# Kasli-SOC_USB_Serial_Quad.net
KiCad netlist of a schematic drawn in Altium Designer
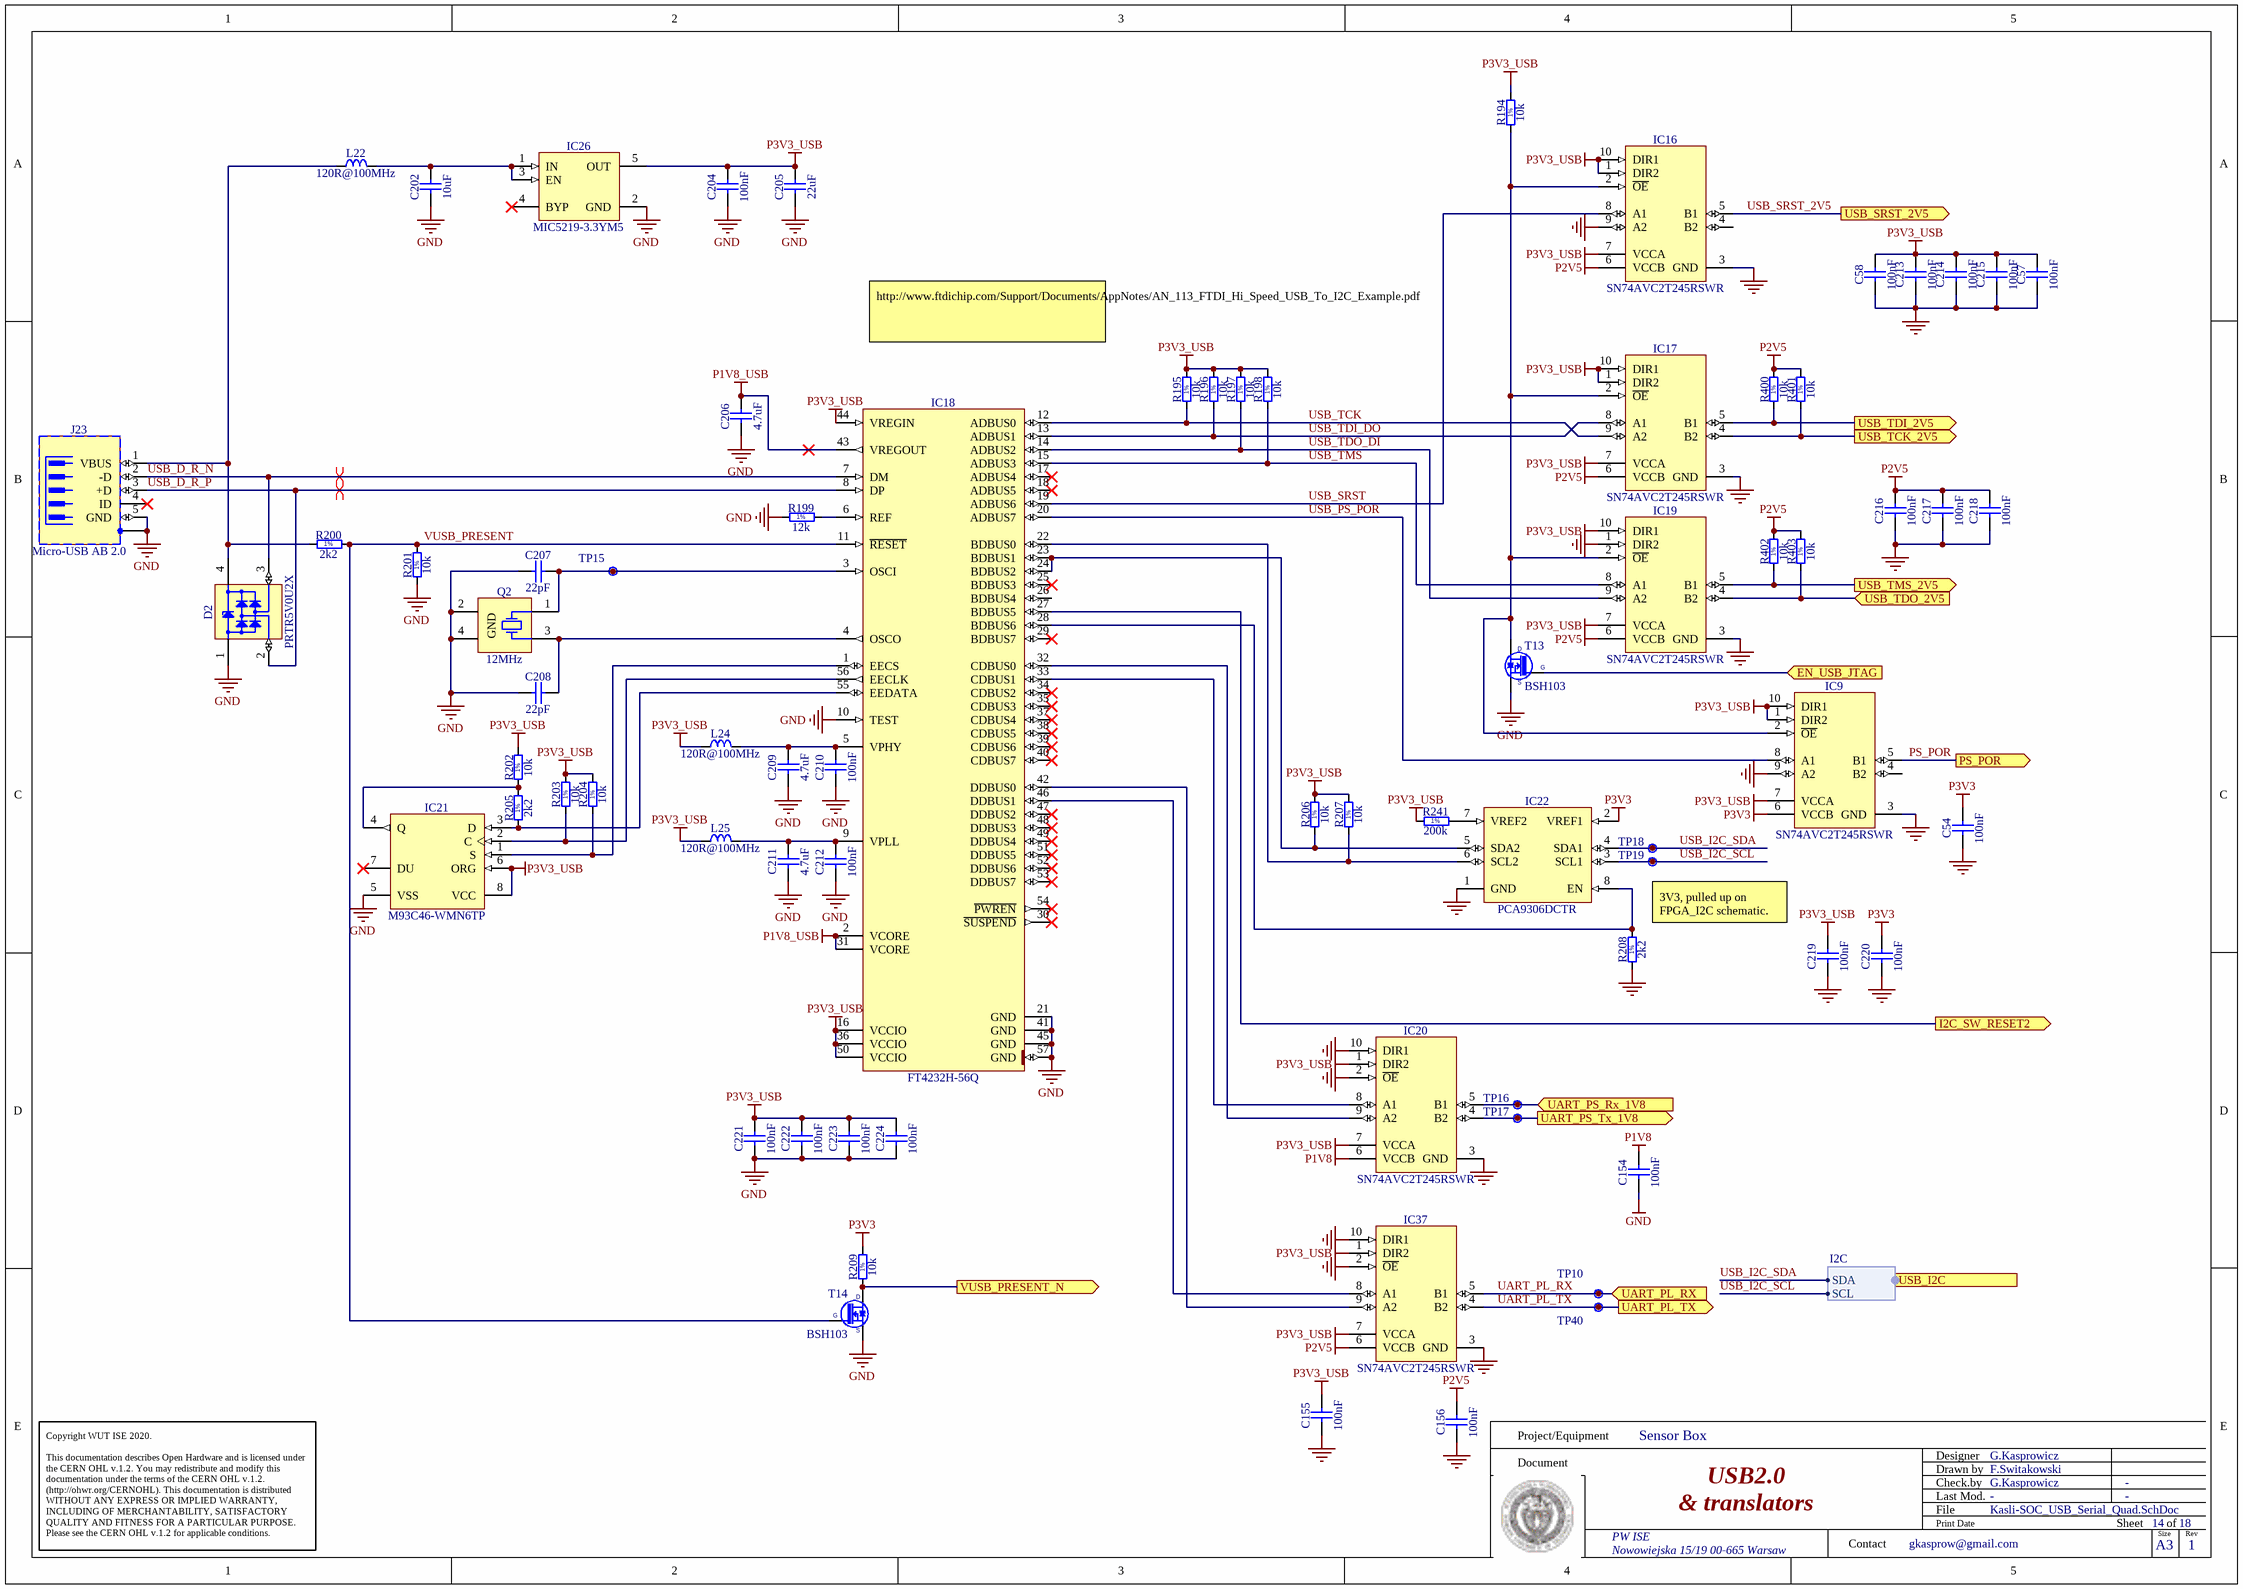
[diagram p0: Kasli-SOC_USB_Serial_Quad.SchDoc]

(export (version "E")
  (design (tool "Eeschema 10.0.6"))
  (components
    (comp (ref "C54")
      (value "100nF")
      (footprint "CAPC1005X55N")
      (description "Non-polarised capacitor")
      (fields
        (field (name "PART NUMBER") "CC0402_100NF_16V_10%_X7R")
        (field (name "VOLTAGE") "16V")
        (field (name "AUTHOR") "CERN DEM JLC")
      )
      (libsource (lib "Capacitors") (part "Capacitor - non polarized"))
    )
    (comp (ref "C57")
      (value "100nF")
      (footprint "CAPC1005X55N")
      (description "Non-polarised capacitor")
      (fields
        (field (name "PART NUMBER") "CC0402_100NF_16V_10%_X7R")
        (field (name "VOLTAGE") "16V")
        (field (name "AUTHOR") "CERN DEM JLC")
      )
      (libsource (lib "Capacitors") (part "Capacitor - non polarized"))
    )
    (comp (ref "C58")
      (value "100nF")
      (footprint "CAPC1005X55N")
      (description "Non-polarised capacitor")
      (fields
        (field (name "PART NUMBER") "CC0402_100NF_16V_10%_X7R")
        (field (name "VOLTAGE") "16V")
        (field (name "AUTHOR") "CERN DEM JLC")
      )
      (libsource (lib "Capacitors") (part "Capacitor - non polarized"))
    )
    (comp (ref "C154")
      (value "100nF")
      (footprint "CAPC1005X55N")
      (description "Non-polarised capacitor")
      (fields
        (field (name "PART NUMBER") "CC0402_100NF_16V_10%_X7R")
        (field (name "VOLTAGE") "16V")
        (field (name "AUTHOR") "CERN DEM JLC")
      )
      (libsource (lib "Capacitors") (part "Capacitor - non polarized"))
    )
    (comp (ref "C155")
      (value "100nF")
      (footprint "CAPC1005X55N")
      (description "Non-polarised capacitor")
      (fields
        (field (name "PART NUMBER") "CC0402_100NF_16V_10%_X7R")
        (field (name "VOLTAGE") "16V")
        (field (name "AUTHOR") "CERN DEM JLC")
      )
      (libsource (lib "Capacitors") (part "Capacitor - non polarized"))
    )
    (comp (ref "C156")
      (value "100nF")
      (footprint "CAPC1005X55N")
      (description "Non-polarised capacitor")
      (fields
        (field (name "PART NUMBER") "CC0402_100NF_16V_10%_X7R")
        (field (name "VOLTAGE") "16V")
        (field (name "AUTHOR") "CERN DEM JLC")
      )
      (libsource (lib "Capacitors") (part "Capacitor - non polarized"))
    )
    (comp (ref "C202")
      (value "10uF")
      (footprint "CAPC1608X87N")
      (description "Non-polarised capacitor")
      (fields
        (field (name "PART NUMBER") "CC0603_10UF_6.3V_20%_X5R")
        (field (name "VOLTAGE") "6.3V")
        (field (name "AUTHOR") "CERN DEM JLC")
      )
      (libsource (lib "Capacitors") (part "Capacitor - non polarized"))
    )
    (comp (ref "C204")
      (value "100nF")
      (footprint "CAPC0603X33N")
      (description "Non-polarised capacitor")
      (fields
        (field (name "PART NUMBER") "CC0201_100NF_6.3V_10%_X5R")
        (field (name "VOLTAGE") "6.3V")
        (field (name "AUTHOR") "CERN DEM JLC")
      )
      (libsource (lib "Capacitors") (part "Capacitor - non polarized"))
    )
    (comp (ref "C205")
      (value "22uF")
      (footprint "CAPC1709X100N")
      (description "Non-polarised capacitor")
      (fields
        (field (name "PART NUMBER") "CC0603_22UF_6.3V_20%_X5R")
        (field (name "VOLTAGE") "6.3V")
        (field (name "AUTHOR") "CERN DEM JLC")
      )
      (libsource (lib "Capacitors") (part "Capacitor - non polarized"))
    )
    (comp (ref "C206")
      (value "4.7uF")
      (footprint "CAPC2012X135N")
      (description "Non-polarised capacitor")
      (fields
        (field (name "PART NUMBER") "CC0805_4.7UF_10V_10%_X5R")
        (field (name "VOLTAGE") "10V")
        (field (name "AUTHOR") "CERN DEM JLC")
      )
      (libsource (lib "Capacitors") (part "Capacitor - non polarized"))
    )
    (comp (ref "C207")
      (value "22pF")
      (footprint "CAPC1005X55N")
      (description "Non-polarised capacitor")
      (fields
        (field (name "PART NUMBER") "CC0402_22PF_50V_5%_C0G")
        (field (name "VOLTAGE") "50V")
        (field (name "AUTHOR") "CERN DEM JLC")
      )
      (libsource (lib "Capacitors") (part "Capacitor - non polarized"))
    )
    (comp (ref "C208")
      (value "22pF")
      (footprint "CAPC1005X55N")
      (description "Non-polarised capacitor")
      (fields
        (field (name "PART NUMBER") "CC0402_22PF_50V_5%_C0G")
        (field (name "VOLTAGE") "50V")
        (field (name "AUTHOR") "CERN DEM JLC")
      )
      (libsource (lib "Capacitors") (part "Capacitor - non polarized"))
    )
    (comp (ref "C209")
      (value "4.7uF")
      (footprint "CAPC2012X135N")
      (description "Non-polarised capacitor")
      (fields
        (field (name "PART NUMBER") "CC0805_4.7UF_10V_10%_X5R")
        (field (name "VOLTAGE") "10V")
        (field (name "AUTHOR") "CERN DEM JLC")
      )
      (libsource (lib "Capacitors") (part "Capacitor - non polarized"))
    )
    (comp (ref "C210")
      (value "100nF")
      (footprint "CAPC0603X33N")
      (description "Non-polarised capacitor")
      (fields
        (field (name "PART NUMBER") "CC0201_100NF_6.3V_10%_X5R")
        (field (name "VOLTAGE") "6.3V")
        (field (name "AUTHOR") "CERN DEM JLC")
      )
      (libsource (lib "Capacitors") (part "Capacitor - non polarized"))
    )
    (comp (ref "C211")
      (value "4.7uF")
      (footprint "CAPC2012X135N")
      (description "Non-polarised capacitor")
      (fields
        (field (name "PART NUMBER") "CC0805_4.7UF_10V_10%_X5R")
        (field (name "VOLTAGE") "10V")
        (field (name "AUTHOR") "CERN DEM JLC")
      )
      (libsource (lib "Capacitors") (part "Capacitor - non polarized"))
    )
    (comp (ref "C212")
      (value "100nF")
      (footprint "CAPC0603X33N")
      (description "Non-polarised capacitor")
      (fields
        (field (name "PART NUMBER") "CC0201_100NF_6.3V_10%_X5R")
        (field (name "VOLTAGE") "6.3V")
        (field (name "AUTHOR") "CERN DEM JLC")
      )
      (libsource (lib "Capacitors") (part "Capacitor - non polarized"))
    )
    (comp (ref "C213")
      (value "100nF")
      (footprint "CAPC1005X55N")
      (description "Non-polarised capacitor")
      (fields
        (field (name "PART NUMBER") "CC0402_100NF_16V_10%_X7R")
        (field (name "VOLTAGE") "16V")
        (field (name "AUTHOR") "CERN DEM JLC")
      )
      (libsource (lib "Capacitors") (part "Capacitor - non polarized"))
    )
    (comp (ref "C214")
      (value "100nF")
      (footprint "CAPC1005X55N")
      (description "Non-polarised capacitor")
      (fields
        (field (name "PART NUMBER") "CC0402_100NF_16V_10%_X7R")
        (field (name "VOLTAGE") "16V")
        (field (name "AUTHOR") "CERN DEM JLC")
      )
      (libsource (lib "Capacitors") (part "Capacitor - non polarized"))
    )
    (comp (ref "C215")
      (value "100nF")
      (footprint "CAPC1005X55N")
      (description "Non-polarised capacitor")
      (fields
        (field (name "PART NUMBER") "CC0402_100NF_16V_10%_X7R")
        (field (name "VOLTAGE") "16V")
        (field (name "AUTHOR") "CERN DEM JLC")
      )
      (libsource (lib "Capacitors") (part "Capacitor - non polarized"))
    )
    (comp (ref "C216")
      (value "100nF")
      (footprint "CAPC1005X55N")
      (description "Non-polarised capacitor")
      (fields
        (field (name "PART NUMBER") "CC0402_100NF_16V_10%_X7R")
        (field (name "VOLTAGE") "16V")
        (field (name "AUTHOR") "CERN DEM JLC")
      )
      (libsource (lib "Capacitors") (part "Capacitor - non polarized"))
    )
    (comp (ref "C217")
      (value "100nF")
      (footprint "CAPC1005X55N")
      (description "Non-polarised capacitor")
      (fields
        (field (name "PART NUMBER") "CC0402_100NF_16V_10%_X7R")
        (field (name "VOLTAGE") "16V")
        (field (name "AUTHOR") "CERN DEM JLC")
      )
      (libsource (lib "Capacitors") (part "Capacitor - non polarized"))
    )
    (comp (ref "C218")
      (value "100nF")
      (footprint "CAPC1005X55N")
      (description "Non-polarised capacitor")
      (fields
        (field (name "PART NUMBER") "CC0402_100NF_16V_10%_X7R")
        (field (name "VOLTAGE") "16V")
        (field (name "AUTHOR") "CERN DEM JLC")
      )
      (libsource (lib "Capacitors") (part "Capacitor - non polarized"))
    )
    (comp (ref "C219")
      (value "100nF")
      (footprint "CAPC1005X55N")
      (description "Non-polarised capacitor")
      (fields
        (field (name "PART NUMBER") "CC0402_100NF_16V_10%_X7R")
        (field (name "VOLTAGE") "16V")
        (field (name "AUTHOR") "CERN DEM JLC")
      )
      (libsource (lib "Capacitors") (part "Capacitor - non polarized"))
    )
    (comp (ref "C220")
      (value "100nF")
      (footprint "CAPC1005X55N")
      (description "Non-polarised capacitor")
      (fields
        (field (name "PART NUMBER") "CC0402_100NF_16V_10%_X7R")
        (field (name "VOLTAGE") "16V")
        (field (name "AUTHOR") "CERN DEM JLC")
      )
      (libsource (lib "Capacitors") (part "Capacitor - non polarized"))
    )
    (comp (ref "C221")
      (value "100nF")
      (footprint "CAPC1005X55N")
      (description "Non-polarised capacitor")
      (fields
        (field (name "PART NUMBER") "CC0402_100NF_16V_10%_X7R")
        (field (name "VOLTAGE") "16V")
        (field (name "AUTHOR") "CERN DEM JLC")
      )
      (libsource (lib "Capacitors") (part "Capacitor - non polarized"))
    )
    (comp (ref "C222")
      (value "100nF")
      (footprint "CAPC1005X55N")
      (description "Non-polarised capacitor")
      (fields
        (field (name "PART NUMBER") "CC0402_100NF_16V_10%_X7R")
        (field (name "VOLTAGE") "16V")
        (field (name "AUTHOR") "CERN DEM JLC")
      )
      (libsource (lib "Capacitors") (part "Capacitor - non polarized"))
    )
    (comp (ref "C223")
      (value "100nF")
      (footprint "CAPC1005X55N")
      (description "Non-polarised capacitor")
      (fields
        (field (name "PART NUMBER") "CC0402_100NF_16V_10%_X7R")
        (field (name "VOLTAGE") "16V")
        (field (name "AUTHOR") "CERN DEM JLC")
      )
      (libsource (lib "Capacitors") (part "Capacitor - non polarized"))
    )
    (comp (ref "C224")
      (value "100nF")
      (footprint "CAPC1005X55N")
      (description "Non-polarised capacitor")
      (fields
        (field (name "PART NUMBER") "CC0402_100NF_16V_10%_X7R")
        (field (name "VOLTAGE") "16V")
        (field (name "AUTHOR") "CERN DEM JLC")
      )
      (libsource (lib "Capacitors") (part "Capacitor - non polarized"))
    )
    (comp (ref "D2")
      (value "PRTR5V0U2X")
      (footprint "SOT190P230X110-4N")
      (description "Ultra Low Capacitance Double Rail-to-Rail ESD Protection Diode")
      (fields
        (field (name "VOLTAGE") "5.5V")
        (field (name "MANUFACTURER") "NXP SEMICONDUCTORS")
        (field (name "AUTHOR") "CERN DEM JLC")
      )
      (libsource (lib "ICs And Semiconductors") (part "PRTR5V0U2X"))
    )
    (comp (ref "IC9")
      (value "SN74AVC2T245RSWR")
      (footprint "QFN40P140X180X55-10N")
      (description "Dual-Bit Dual-Supply Bus Transceiver With Configurable Voltage Translation and 3-State Outputs")
      (fields (field (name "MANUFACTURER") "TEXAS INSTRUMENTS") (field (name "AUTHOR") "CERN DEM JLC"))
      (libsource (lib "ICs And Semiconductors") (part "742T245"))
    )
    (comp (ref "IC16")
      (value "SN74AVC2T245RSWR")
      (footprint "QFN40P140X180X55-10N")
      (description "Dual-Bit Dual-Supply Bus Transceiver With Configurable Voltage Translation and 3-State Outputs")
      (fields (field (name "MANUFACTURER") "TEXAS INSTRUMENTS") (field (name "AUTHOR") "CERN DEM JLC"))
      (libsource (lib "ICs And Semiconductors") (part "742T245"))
    )
    (comp (ref "IC17")
      (value "SN74AVC2T245RSWR")
      (footprint "QFN40P140X180X55-10N")
      (description "Dual-Bit Dual-Supply Bus Transceiver With Configurable Voltage Translation and 3-State Outputs")
      (fields (field (name "MANUFACTURER") "TEXAS INSTRUMENTS") (field (name "AUTHOR") "CERN DEM JLC"))
      (libsource (lib "ICs And Semiconductors") (part "742T245"))
    )
    (comp (ref "IC18")
      (value "FT4232H-56Q")
      (footprint "QFN50P800X800X100-57N-S620")
      (description "Quad High Speed USB to Multipurpose UART/MPSSE IC")
      (fields
        (field (name "MANUFACTURER") "FUTURE TECHNOLOGY DEVICES INTERNATIONAL (FTDI)")
        (field (name "AUTHOR") "CERN DEM JLC")
      )
      (libsource (lib "ICs And Semiconductors") (part "FT4232H-56Q"))
    )
    (comp (ref "IC19")
      (value "SN74AVC2T245RSWR")
      (footprint "QFN40P140X180X55-10N")
      (description "Dual-Bit Dual-Supply Bus Transceiver With Configurable Voltage Translation and 3-State Outputs")
      (fields (field (name "MANUFACTURER") "TEXAS INSTRUMENTS") (field (name "AUTHOR") "CERN DEM JLC"))
      (libsource (lib "ICs And Semiconductors") (part "742T245"))
    )
    (comp (ref "IC20")
      (value "SN74AVC2T245RSWR")
      (footprint "QFN40P140X180X55-10N")
      (description "Dual-Bit Dual-Supply Bus Transceiver With Configurable Voltage Translation and 3-State Outputs")
      (fields (field (name "MANUFACTURER") "TEXAS INSTRUMENTS") (field (name "AUTHOR") "CERN DEM JLC"))
      (libsource (lib "ICs And Semiconductors") (part "742T245"))
    )
    (comp (ref "IC21")
      (value "M93C46-WMN6TP")
      (footprint "SOIC127P600X175-8N")
      (description "2.5 to 5.5 V, 1Kb (128x8) Serial Microwire Bus EEPROM")
      (fields (field (name "MANUFACTURER") "ST MICROELECTRONICS") (field (name "AUTHOR") "CERN DEM JLC"))
      (libsource (lib "ICs And Semiconductors") (part "M93C46-WMN6TP"))
    )
    (comp (ref "IC22")
      (value "PCA9306DCTR")
      (footprint "SOP65P400X130-8N")
      (description "Dual Bidirectional I2C Bus And SMBus Voltage-Level Translator")
      (fields (field (name "MANUFACTURER") "TEXAS INSTRUMENTS") (field (name "AUTHOR") "CERN DEM JLC"))
      (libsource (lib "ICs And Semiconductors") (part "PCA9306D"))
    )
    (comp (ref "IC26")
      (value "MIC5219-3.3YM5")
      (footprint "SOT95P280X145-5N")
      (description "500mA Peak Output LDO Regulator")
      (fields (field (name "MANUFACTURER") "MICROCHIP TECHNOLOGY") (field (name "AUTHOR") "CERN DEM WB"))
      (libsource (lib "ICs And Semiconductors") (part "MIC5219-X.XYM5"))
    )
    (comp (ref "IC37")
      (value "SN74AVC2T245RSWR")
      (footprint "QFN40P140X180X55-10N")
      (description "Dual-Bit Dual-Supply Bus Transceiver With Configurable Voltage Translation and 3-State Outputs")
      (fields (field (name "MANUFACTURER") "TEXAS INSTRUMENTS") (field (name "AUTHOR") "CERN DEM JLC"))
      (libsource (lib "ICs And Semiconductors") (part "742T245"))
    )
    (comp (ref "J23")
      (value "Micro-USB AB 2.0")
      (footprint "HIROSE_ZX62RD-AB-5P8")
      (description "5 Pin + 1 Shield USB Receptacle")
      (fields
        (field (name "PART NUMBER") "HIROSE_ZX62RD-AB-5P8")
        (field (name "MANUFACTURER") "HIROSE (HRS)")
        (field (name "AUTHOR") "CERN DEM JLC")
      )
      (libsource (lib "Connectors") (part "Connector USB 5 Pin + 1Shield"))
    )
    (comp (ref "L22")
      (value "120R@100MHz")
      (footprint "INDC1608X65N")
      (description "Inductor")
      (fields
        (field (name "PART NUMBER") "IND0603_MURATA_BLM18SG121TN1D")
        (field (name "POWER") "3A")
        (field (name "AUTHOR") "CERN DEM JLC")
      )
      (libsource (lib "Inductors & Transformers") (part "Inductor"))
    )
    (comp (ref "L24")
      (value "120R@100MHz")
      (footprint "INDC1608X65N")
      (description "Inductor")
      (fields
        (field (name "PART NUMBER") "IND0603_MURATA_BLM18SG121TN1D")
        (field (name "POWER") "3A")
        (field (name "AUTHOR") "CERN DEM JLC")
      )
      (libsource (lib "Inductors & Transformers") (part "Inductor"))
    )
    (comp (ref "L25")
      (value "120R@100MHz")
      (footprint "INDC1608X65N")
      (description "Inductor")
      (fields
        (field (name "PART NUMBER") "IND0603_MURATA_BLM18SG121TN1D")
        (field (name "POWER") "3A")
        (field (name "AUTHOR") "CERN DEM JLC")
      )
      (libsource (lib "Inductors & Transformers") (part "Inductor"))
    )
    (comp (ref "Q2")
      (value "12MHz")
      (footprint "XTAL_TXC_7M")
      (description "Crystal 4 pins 1=XTAL Control 2=GND3=XTAL 4=GND")
      (fields
        (field (name "PART NUMBER") "XTAL_12MHZ_TXC_7M-12.000MAAJ-T")
        (field (name "MANUFACTURER") "TXC CORPORATION")
        (field (name "AUTHOR") "CERN DEM JLC")
      )
      (libsource (lib "ICs And Semiconductors") (part "Quartz Crystal 1X 2GND 3X 4GND"))
    )
    (comp (ref "R194")
      (value "10k")
      (footprint "RESC1005X40N")
      (description "Resistor - 1%")
      (fields
        (field (name "PART NUMBER") "R0402_10K_1%_0.0625W_100PPM")
        (field (name "POWER") "0.0625W")
        (field (name "AUTHOR") "CERN DEM JLC")
      )
      (libsource (lib "Resistors") (part "Resistor - 1%"))
    )
    (comp (ref "R195")
      (value "10k")
      (footprint "RESC1005X40N")
      (description "Resistor - 1%")
      (fields
        (field (name "PART NUMBER") "R0402_10K_1%_0.0625W_100PPM")
        (field (name "POWER") "0.0625W")
        (field (name "AUTHOR") "CERN DEM JLC")
      )
      (libsource (lib "Resistors") (part "Resistor - 1%"))
    )
    (comp (ref "R196")
      (value "10k")
      (footprint "RESC1005X40N")
      (description "Resistor - 1%")
      (fields
        (field (name "PART NUMBER") "R0402_10K_1%_0.0625W_100PPM")
        (field (name "POWER") "0.0625W")
        (field (name "AUTHOR") "CERN DEM JLC")
      )
      (libsource (lib "Resistors") (part "Resistor - 1%"))
    )
    (comp (ref "R197")
      (value "10k")
      (footprint "RESC1005X40N")
      (description "Resistor - 1%")
      (fields
        (field (name "PART NUMBER") "R0402_10K_1%_0.0625W_100PPM")
        (field (name "POWER") "0.0625W")
        (field (name "AUTHOR") "CERN DEM JLC")
      )
      (libsource (lib "Resistors") (part "Resistor - 1%"))
    )
    (comp (ref "R198")
      (value "10k")
      (footprint "RESC1005X40N")
      (description "Resistor - 1%")
      (fields
        (field (name "PART NUMBER") "R0402_10K_1%_0.0625W_100PPM")
        (field (name "POWER") "0.0625W")
        (field (name "AUTHOR") "CERN DEM JLC")
      )
      (libsource (lib "Resistors") (part "Resistor - 1%"))
    )
    (comp (ref "R199")
      (value "12k")
      (footprint "RESC1005X40N")
      (description "Resistor - 1%")
      (fields
        (field (name "PART NUMBER") "R0402_12K_1%_0.0625W_100PPM")
        (field (name "POWER") "0.0625W")
        (field (name "AUTHOR") "CERN DEM JLC")
      )
      (libsource (lib "Resistors") (part "Resistor - 1%"))
    )
    (comp (ref "R200")
      (value "2k2")
      (footprint "RESC1005X40N")
      (description "Resistor - 1%")
      (fields
        (field (name "PART NUMBER") "R0402_2K2_1%_0.0625W_100PPM")
        (field (name "POWER") "0.0625W")
        (field (name "AUTHOR") "CERN DEM JLC")
      )
      (libsource (lib "Resistors") (part "Resistor - 1%"))
    )
    (comp (ref "R201")
      (value "10k")
      (footprint "RESC1005X40N")
      (description "Resistor - 1%")
      (fields
        (field (name "PART NUMBER") "R0402_10K_1%_0.0625W_100PPM")
        (field (name "POWER") "0.0625W")
        (field (name "AUTHOR") "CERN DEM JLC")
      )
      (libsource (lib "Resistors") (part "Resistor - 1%"))
    )
    (comp (ref "R202")
      (value "10k")
      (footprint "RESC1005X40N")
      (description "Resistor - 1%")
      (fields
        (field (name "PART NUMBER") "R0402_10K_1%_0.0625W_100PPM")
        (field (name "POWER") "0.0625W")
        (field (name "AUTHOR") "CERN DEM JLC")
      )
      (libsource (lib "Resistors") (part "Resistor - 1%"))
    )
    (comp (ref "R203")
      (value "10k")
      (footprint "RESC1005X40N")
      (description "Resistor - 1%")
      (fields
        (field (name "PART NUMBER") "R0402_10K_1%_0.0625W_100PPM")
        (field (name "POWER") "0.0625W")
        (field (name "AUTHOR") "CERN DEM JLC")
      )
      (libsource (lib "Resistors") (part "Resistor - 1%"))
    )
    (comp (ref "R204")
      (value "10k")
      (footprint "RESC1005X40N")
      (description "Resistor - 1%")
      (fields
        (field (name "PART NUMBER") "R0402_10K_1%_0.0625W_100PPM")
        (field (name "POWER") "0.0625W")
        (field (name "AUTHOR") "CERN DEM JLC")
      )
      (libsource (lib "Resistors") (part "Resistor - 1%"))
    )
    (comp (ref "R205")
      (value "2k2")
      (footprint "RESC1005X40N")
      (description "Resistor - 1%")
      (fields
        (field (name "PART NUMBER") "R0402_2K2_1%_0.0625W_100PPM")
        (field (name "POWER") "0.0625W")
        (field (name "AUTHOR") "CERN DEM JLC")
      )
      (libsource (lib "Resistors") (part "Resistor - 1%"))
    )
    (comp (ref "R206")
      (value "10k")
      (footprint "RESC1005X40N")
      (description "Resistor - 1%")
      (fields
        (field (name "PART NUMBER") "R0402_10K_1%_0.0625W_100PPM")
        (field (name "POWER") "0.0625W")
        (field (name "AUTHOR") "CERN DEM JLC")
      )
      (libsource (lib "Resistors") (part "Resistor - 1%"))
    )
    (comp (ref "R207")
      (value "10k")
      (footprint "RESC1005X40N")
      (description "Resistor - 1%")
      (fields
        (field (name "PART NUMBER") "R0402_10K_1%_0.0625W_100PPM")
        (field (name "POWER") "0.0625W")
        (field (name "AUTHOR") "CERN DEM JLC")
      )
      (libsource (lib "Resistors") (part "Resistor - 1%"))
    )
    (comp (ref "R208")
      (value "2k2")
      (footprint "RESC1005X40N")
      (description "Resistor - 1%")
      (fields
        (field (name "PART NUMBER") "R0402_2K2_1%_0.0625W_100PPM")
        (field (name "POWER") "0.0625W")
        (field (name "AUTHOR") "CERN DEM JLC")
      )
      (libsource (lib "Resistors") (part "Resistor - 1%"))
    )
    (comp (ref "R209")
      (value "10k")
      (footprint "RESC1005X40N")
      (description "Resistor - 1%")
      (fields
        (field (name "PART NUMBER") "R0402_10K_1%_0.0625W_100PPM")
        (field (name "POWER") "0.0625W")
        (field (name "AUTHOR") "CERN DEM JLC")
      )
      (libsource (lib "Resistors") (part "Resistor - 1%"))
    )
    (comp (ref "R241")
      (value "200k")
      (footprint "RESC1005X40N")
      (description "Resistor - 1%")
      (fields
        (field (name "PART NUMBER") "R0402_200K_1%_0.0625W_100PPM")
        (field (name "POWER") "0.0625W")
        (field (name "AUTHOR") "CERN DEM JLC")
      )
      (libsource (lib "Resistors") (part "Resistor - 1%"))
    )
    (comp (ref "R400")
      (value "10k")
      (footprint "RESC1005X40N")
      (description "Resistor - 1%")
      (fields
        (field (name "PART NUMBER") "R0402_10K_1%_0.0625W_100PPM")
        (field (name "POWER") "0.0625W")
        (field (name "AUTHOR") "CERN DEM JLC")
      )
      (libsource (lib "Resistors") (part "Resistor - 1%"))
    )
    (comp (ref "R401")
      (value "10k")
      (footprint "RESC1005X40N")
      (description "Resistor - 1%")
      (fields
        (field (name "PART NUMBER") "R0402_10K_1%_0.0625W_100PPM")
        (field (name "POWER") "0.0625W")
        (field (name "AUTHOR") "CERN DEM JLC")
      )
      (libsource (lib "Resistors") (part "Resistor - 1%"))
    )
    (comp (ref "R402")
      (value "10k")
      (footprint "RESC1005X40N")
      (description "Resistor - 1%")
      (fields
        (field (name "PART NUMBER") "R0402_10K_1%_0.0625W_100PPM")
        (field (name "POWER") "0.0625W")
        (field (name "AUTHOR") "CERN DEM JLC")
      )
      (libsource (lib "Resistors") (part "Resistor - 1%"))
    )
    (comp (ref "R403")
      (value "10k")
      (footprint "RESC1005X40N")
      (description "Resistor - 1%")
      (fields
        (field (name "PART NUMBER") "R0402_10K_1%_0.0625W_100PPM")
        (field (name "POWER") "0.0625W")
        (field (name "AUTHOR") "CERN DEM JLC")
      )
      (libsource (lib "Resistors") (part "Resistor - 1%"))
    )
    (comp (ref "T13")
      (value "BSH103")
      (footprint "SOT95P230X110-3N")
      (description "N-CHANNEL MOSFET WITH DIODE")
      (fields (field (name "MANUFACTURER") "NEXPERIA") (field (name "AUTHOR") "CERN DEM JLC"))
      (libsource (lib "") (part "N-MOSFET-D 1G 2S 3D_1"))
    )
    (comp (ref "T14")
      (value "BSH103")
      (footprint "SOT95P230X110-3N")
      (description "N-CHANNEL MOSFET WITH DIODE")
      (fields (field (name "MANUFACTURER") "NEXPERIA") (field (name "AUTHOR") "CERN DEM JLC"))
      (libsource (lib "ICs And Semiconductors") (part "N-MOSFET-D 1G 2S 3D"))
    )
    (comp (ref "TP10")
      (value "RxD")
      (footprint "TPS127")
      (description "Test Point")
      (fields (field (name "PART NUMBER") "SMD_PAD_1.27X1.27MM") (field (name "AUTHOR") "CERN DEM JLC"))
      (libsource (lib "Eletro-mechanical") (part "Test Point"))
    )
    (comp (ref "TP15")
      (value "Q2")
      (footprint "TPS127")
      (description "Test Point")
      (fields (field (name "PART NUMBER") "SMD_PAD_1.27X1.27MM") (field (name "AUTHOR") "CERN DEM JLC"))
      (libsource (lib "Eletro-mechanical") (part "Test Point"))
    )
    (comp (ref "TP16")
      (value "RxD")
      (footprint "TPS127")
      (description "Test Point")
      (fields (field (name "PART NUMBER") "SMD_PAD_1.27X1.27MM") (field (name "AUTHOR") "CERN DEM JLC"))
      (libsource (lib "Eletro-mechanical") (part "Test Point"))
    )
    (comp (ref "TP17")
      (value "TxD")
      (footprint "TPS127")
      (description "Test Point")
      (fields (field (name "PART NUMBER") "SMD_PAD_1.27X1.27MM") (field (name "AUTHOR") "CERN DEM JLC"))
      (libsource (lib "Eletro-mechanical") (part "Test Point"))
    )
    (comp (ref "TP18")
      (value "USB I2C SDA")
      (footprint "TPS127")
      (description "Test Point")
      (fields (field (name "PART NUMBER") "SMD_PAD_1.27X1.27MM") (field (name "AUTHOR") "CERN DEM JLC"))
      (libsource (lib "Eletro-mechanical") (part "Test Point"))
    )
    (comp (ref "TP19")
      (value "USB I2C SCL")
      (footprint "TPS127")
      (description "Test Point")
      (fields (field (name "PART NUMBER") "SMD_PAD_1.27X1.27MM") (field (name "AUTHOR") "CERN DEM JLC"))
      (libsource (lib "Eletro-mechanical") (part "Test Point"))
    )
    (comp (ref "TP40")
      (value "TxD")
      (footprint "TPS127")
      (description "Test Point")
      (fields (field (name "PART NUMBER") "SMD_PAD_1.27X1.27MM") (field (name "AUTHOR") "CERN DEM JLC"))
      (libsource (lib "Eletro-mechanical") (part "Test Point"))
    )
  )
  (nets
    (net (code "2") (name "/EN_USB_JTAG") (class "Default")
      (node (ref "T13") (pin "1") (pinfunction "G_1") (pintype "passive"))
    )
    (net (code "3") (name "/I2C_SW_RESET2") (class "Default")
      (node (ref "IC18") (pin "27") (pinfunction "BDBUS5_27") (pintype "bidirectional"))
    )
    (net (code "4") (name "/PS_POR") (class "Default")
      (node (ref "IC9") (pin "5") (pinfunction "B1_5") (pintype "bidirectional"))
    )
    (net (code "5") (name "/UART_PL_RX") (class "Default")
      (node (ref "IC37") (pin "5") (pinfunction "B1_5") (pintype "bidirectional"))
      (node (ref "TP10") (pin "1") (pinfunction "1_1") (pintype "bidirectional"))
    )
    (net (code "6") (name "/UART_PL_TX") (class "Default")
      (node (ref "IC37") (pin "4") (pinfunction "B2_4") (pintype "bidirectional"))
      (node (ref "TP40") (pin "1") (pinfunction "1_1") (pintype "bidirectional"))
    )
    (net (code "7") (name "/UART_PS_Rx_1V8") (class "Default")
      (node (ref "IC20") (pin "5") (pinfunction "B1_5") (pintype "bidirectional"))
      (node (ref "TP16") (pin "1") (pinfunction "1_1") (pintype "bidirectional"))
    )
    (net (code "8") (name "/UART_PS_Tx_1V8") (class "Default")
      (node (ref "IC20") (pin "4") (pinfunction "B2_4") (pintype "bidirectional"))
      (node (ref "TP17") (pin "1") (pinfunction "1_1") (pintype "bidirectional"))
    )
    (net (code "9") (name "/USB_D_R_N") (class "Default")
      (node (ref "D2") (pin "3") (pinfunction "I/O2_3") (pintype "bidirectional"))
      (node (ref "IC18") (pin "7") (pinfunction "DM_7") (pintype "input"))
      (node (ref "J23") (pin "2") (pinfunction "-D_2") (pintype "bidirectional"))
    )
    (net (code "10") (name "/USB_D_R_P") (class "Default")
      (node (ref "D2") (pin "2") (pinfunction "I/O1_2") (pintype "bidirectional"))
      (node (ref "IC18") (pin "8") (pinfunction "DP_8") (pintype "input"))
      (node (ref "J23") (pin "3") (pinfunction "+D_3") (pintype "bidirectional"))
    )
    (net (code "11") (name "/USB_I2C_SCL") (class "Default")
      (node (ref "IC22") (pin "3") (pinfunction "SCL1_3") (pintype "bidirectional"))
      (node (ref "TP19") (pin "1") (pinfunction "1_1") (pintype "bidirectional"))
    )
    (net (code "12") (name "/USB_I2C_SDA") (class "Default")
      (node (ref "IC22") (pin "4") (pinfunction "SDA1_4") (pintype "bidirectional"))
      (node (ref "TP18") (pin "1") (pinfunction "1_1") (pintype "bidirectional"))
    )
    (net (code "13") (name "/USB_PS_POR") (class "Default")
      (node (ref "IC18") (pin "20") (pinfunction "ADBUS7_20") (pintype "bidirectional"))
      (node (ref "IC9") (pin "8") (pinfunction "A1_8") (pintype "bidirectional"))
    )
    (net (code "14") (name "/USB_SRST") (class "Default")
      (node (ref "IC16") (pin "8") (pinfunction "A1_8") (pintype "bidirectional"))
      (node (ref "IC18") (pin "19") (pinfunction "ADBUS6_19") (pintype "bidirectional"))
    )
    (net (code "15") (name "/USB_SRST_2V5") (class "Default")
      (node (ref "IC16") (pin "5") (pinfunction "B1_5") (pintype "bidirectional"))
    )
    (net (code "16") (name "/USB_TCK") (class "Default")
      (node (ref "IC17") (pin "9") (pinfunction "A2_9") (pintype "bidirectional"))
      (node (ref "IC18") (pin "12") (pinfunction "ADBUS0_12") (pintype "bidirectional"))
      (node (ref "R195") (pin "1") (pinfunction "1_1") (pintype "passive"))
    )
    (net (code "17") (name "/USB_TCK_2V5") (class "Default")
      (node (ref "IC17") (pin "4") (pinfunction "B2_4") (pintype "bidirectional"))
      (node (ref "R401") (pin "1") (pinfunction "1_1") (pintype "passive"))
    )
    (net (code "18") (name "/USB_TDI_2V5") (class "Default")
      (node (ref "IC17") (pin "5") (pinfunction "B1_5") (pintype "bidirectional"))
      (node (ref "R400") (pin "1") (pinfunction "1_1") (pintype "passive"))
    )
    (net (code "19") (name "/USB_TDI_DO") (class "Default")
      (node (ref "IC17") (pin "8") (pinfunction "A1_8") (pintype "bidirectional"))
      (node (ref "IC18") (pin "13") (pinfunction "ADBUS1_13") (pintype "bidirectional"))
      (node (ref "R196") (pin "1") (pinfunction "1_1") (pintype "passive"))
    )
    (net (code "20") (name "/USB_TDO_2V5") (class "Default")
      (node (ref "IC19") (pin "4") (pinfunction "B2_4") (pintype "bidirectional"))
      (node (ref "R403") (pin "1") (pinfunction "1_1") (pintype "passive"))
    )
    (net (code "21") (name "/USB_TDO_DI") (class "Default")
      (node (ref "IC18") (pin "14") (pinfunction "ADBUS2_14") (pintype "bidirectional"))
      (node (ref "IC19") (pin "9") (pinfunction "A2_9") (pintype "bidirectional"))
      (node (ref "R197") (pin "1") (pinfunction "1_1") (pintype "passive"))
    )
    (net (code "22") (name "/USB_TMS") (class "Default")
      (node (ref "IC18") (pin "15") (pinfunction "ADBUS3_15") (pintype "bidirectional"))
      (node (ref "IC19") (pin "8") (pinfunction "A1_8") (pintype "bidirectional"))
      (node (ref "R198") (pin "1") (pinfunction "1_1") (pintype "passive"))
    )
    (net (code "23") (name "/USB_TMS_2V5") (class "Default")
      (node (ref "IC19") (pin "5") (pinfunction "B1_5") (pintype "bidirectional"))
      (node (ref "R402") (pin "1") (pinfunction "1_1") (pintype "passive"))
    )
    (net (code "24") (name "/VUSB_PRESENT") (class "Default")
      (node (ref "IC18") (pin "11") (pinfunction "~{RESET}_11") (pintype "input"))
      (node (ref "R200") (pin "2") (pinfunction "2_2") (pintype "passive"))
      (node (ref "R201") (pin "2") (pinfunction "2_2") (pintype "passive"))
      (node (ref "T14") (pin "1") (pinfunction "G_1") (pintype "passive"))
    )
    (net (code "25") (name "/VUSB_PRESENT_N") (class "Default")
      (node (ref "R209") (pin "1") (pinfunction "1_1") (pintype "passive"))
      (node (ref "T14") (pin "3") (pinfunction "D_3") (pintype "passive"))
    )
    (net (code "27") (name "GND") (class "Default")
      (node (ref "C154") (pin "1") (pinfunction "1_1") (pintype "passive"))
      (node (ref "C155") (pin "1") (pinfunction "1_1") (pintype "passive"))
      (node (ref "C156") (pin "1") (pinfunction "1_1") (pintype "passive"))
      (node (ref "C202") (pin "1") (pinfunction "1_1") (pintype "passive"))
      (node (ref "C204") (pin "1") (pinfunction "1_1") (pintype "passive"))
      (node (ref "C205") (pin "1") (pinfunction "1_1") (pintype "passive"))
      (node (ref "C206") (pin "1") (pinfunction "1_1") (pintype "passive"))
      (node (ref "C207") (pin "1") (pinfunction "1_1") (pintype "passive"))
      (node (ref "C208") (pin "1") (pinfunction "1_1") (pintype "passive"))
      (node (ref "C209") (pin "1") (pinfunction "1_1") (pintype "passive"))
      (node (ref "C210") (pin "1") (pinfunction "1_1") (pintype "passive"))
      (node (ref "C211") (pin "1") (pinfunction "1_1") (pintype "passive"))
      (node (ref "C212") (pin "1") (pinfunction "1_1") (pintype "passive"))
      (node (ref "C213") (pin "1") (pinfunction "1_1") (pintype "passive"))
      (node (ref "C214") (pin "1") (pinfunction "1_1") (pintype "passive"))
      (node (ref "C215") (pin "1") (pinfunction "1_1") (pintype "passive"))
      (node (ref "C216") (pin "1") (pinfunction "1_1") (pintype "passive"))
      (node (ref "C217") (pin "1") (pinfunction "1_1") (pintype "passive"))
      (node (ref "C218") (pin "1") (pinfunction "1_1") (pintype "passive"))
      (node (ref "C219") (pin "1") (pinfunction "1_1") (pintype "passive"))
      (node (ref "C220") (pin "1") (pinfunction "1_1") (pintype "passive"))
      (node (ref "C221") (pin "1") (pinfunction "1_1") (pintype "passive"))
      (node (ref "C222") (pin "1") (pinfunction "1_1") (pintype "passive"))
      (node (ref "C223") (pin "1") (pinfunction "1_1") (pintype "passive"))
      (node (ref "C224") (pin "1") (pinfunction "1_1") (pintype "passive"))
      (node (ref "C54") (pin "1") (pinfunction "1_1") (pintype "passive"))
      (node (ref "C57") (pin "1") (pinfunction "1_1") (pintype "passive"))
      (node (ref "C58") (pin "1") (pinfunction "1_1") (pintype "passive"))
      (node (ref "D2") (pin "1") (pinfunction "GND_1") (pintype "power_in"))
      (node (ref "IC16") (pin "3") (pinfunction "GND_3") (pintype "power_in"))
      (node (ref "IC16") (pin "9") (pinfunction "A2_9") (pintype "bidirectional"))
      (node (ref "IC17") (pin "3") (pinfunction "GND_3") (pintype "power_in"))
      (node (ref "IC18") (pin "10") (pinfunction "TEST_10") (pintype "input"))
      (node (ref "IC18") (pin "21") (pinfunction "GND_21") (pintype "power_in"))
      (node (ref "IC18") (pin "41") (pinfunction "GND_41") (pintype "power_in"))
      (node (ref "IC18") (pin "45") (pinfunction "GND_45") (pintype "power_in"))
      (node (ref "IC18") (pin "57") (pinfunction "GND_57") (pintype "bidirectional"))
      (node (ref "IC19") (pin "1") (pinfunction "DIR2_1") (pintype "input"))
      (node (ref "IC19") (pin "3") (pinfunction "GND_3") (pintype "power_in"))
      (node (ref "IC20") (pin "10") (pinfunction "DIR1_10") (pintype "input"))
      (node (ref "IC20") (pin "2") (pinfunction "~{OE}_2") (pintype "input"))
      (node (ref "IC20") (pin "3") (pinfunction "GND_3") (pintype "power_in"))
      (node (ref "IC21") (pin "5") (pinfunction "VSS_5") (pintype "power_in"))
      (node (ref "IC22") (pin "1") (pinfunction "GND_1") (pintype "power_in"))
      (node (ref "IC26") (pin "2") (pinfunction "GND_2") (pintype "power_in"))
      (node (ref "IC37") (pin "10") (pinfunction "DIR1_10") (pintype "input"))
      (node (ref "IC37") (pin "2") (pinfunction "~{OE}_2") (pintype "input"))
      (node (ref "IC37") (pin "3") (pinfunction "GND_3") (pintype "power_in"))
      (node (ref "IC9") (pin "3") (pinfunction "GND_3") (pintype "power_in"))
      (node (ref "IC9") (pin "9") (pinfunction "A2_9") (pintype "bidirectional"))
      (node (ref "J23") (pin "5") (pinfunction "GND_5") (pintype "bidirectional"))
      (node (ref "J23") (pin "6") (pinfunction "SH_6") (pintype "power_in"))
      (node (ref "Q2") (pin "2") (pinfunction "GND_2") (pintype "power_in"))
      (node (ref "Q2") (pin "4") (pinfunction "GND_4") (pintype "power_in"))
      (node (ref "R199") (pin "1") (pinfunction "1_1") (pintype "passive"))
      (node (ref "R201") (pin "1") (pinfunction "1_1") (pintype "passive"))
      (node (ref "R208") (pin "1") (pinfunction "1_1") (pintype "passive"))
      (node (ref "T13") (pin "2") (pinfunction "S_2") (pintype "passive"))
      (node (ref "T14") (pin "2") (pinfunction "S_2") (pintype "passive"))
    )
    (net (code "28") (name "Net-(D2-VCC)") (class "Default")
      (node (ref "D2") (pin "4") (pinfunction "VCC_4") (pintype "power_in"))
      (node (ref "J23") (pin "1") (pinfunction "VBUS_1") (pintype "bidirectional"))
      (node (ref "L22") (pin "1") (pinfunction "1_1") (pintype "passive"))
      (node (ref "R200") (pin "1") (pinfunction "1_1") (pintype "passive"))
    )
    (net (code "29") (name "Net-(IC16-~{OE})") (class "Default")
      (node (ref "IC16") (pin "2") (pinfunction "~{OE}_2") (pintype "input"))
      (node (ref "IC17") (pin "2") (pinfunction "~{OE}_2") (pintype "input"))
      (node (ref "IC19") (pin "2") (pinfunction "~{OE}_2") (pintype "input"))
      (node (ref "IC9") (pin "2") (pinfunction "~{OE}_2") (pintype "input"))
      (node (ref "R194") (pin "1") (pinfunction "1_1") (pintype "passive"))
      (node (ref "T13") (pin "3") (pinfunction "D_3") (pintype "passive"))
    )
    (net (code "30") (name "Net-(IC18-BDBUS0)") (class "Default")
      (node (ref "IC18") (pin "22") (pinfunction "BDBUS0_22") (pintype "bidirectional"))
      (node (ref "IC22") (pin "6") (pinfunction "SCL2_6") (pintype "bidirectional"))
      (node (ref "R207") (pin "1") (pinfunction "1_1") (pintype "passive"))
    )
    (net (code "31") (name "Net-(IC18-BDBUS1)") (class "Default")
      (node (ref "IC18") (pin "23") (pinfunction "BDBUS1_23") (pintype "bidirectional"))
      (node (ref "IC18") (pin "24") (pinfunction "BDBUS2_24") (pintype "bidirectional"))
      (node (ref "IC22") (pin "5") (pinfunction "SDA2_5") (pintype "bidirectional"))
      (node (ref "R206") (pin "1") (pinfunction "1_1") (pintype "passive"))
    )
    (net (code "32") (name "Net-(IC18-BDBUS6)") (class "Default")
      (node (ref "IC18") (pin "28") (pinfunction "BDBUS6_28") (pintype "bidirectional"))
      (node (ref "IC22") (pin "8") (pinfunction "EN_8") (pintype "input"))
      (node (ref "R208") (pin "2") (pinfunction "2_2") (pintype "passive"))
    )
    (net (code "33") (name "Net-(IC18-CDBUS0)") (class "Default")
      (node (ref "IC18") (pin "32") (pinfunction "CDBUS0_32") (pintype "bidirectional"))
      (node (ref "IC20") (pin "9") (pinfunction "A2_9") (pintype "bidirectional"))
    )
    (net (code "34") (name "Net-(IC18-CDBUS1)") (class "Default")
      (node (ref "IC18") (pin "33") (pinfunction "CDBUS1_33") (pintype "bidirectional"))
      (node (ref "IC20") (pin "8") (pinfunction "A1_8") (pintype "bidirectional"))
    )
    (net (code "35") (name "Net-(IC18-DDBUS0)") (class "Default")
      (node (ref "IC18") (pin "42") (pinfunction "DDBUS0_42") (pintype "bidirectional"))
      (node (ref "IC37") (pin "9") (pinfunction "A2_9") (pintype "bidirectional"))
    )
    (net (code "36") (name "Net-(IC18-DDBUS1)") (class "Default")
      (node (ref "IC18") (pin "46") (pinfunction "DDBUS1_46") (pintype "bidirectional"))
      (node (ref "IC37") (pin "8") (pinfunction "A1_8") (pintype "bidirectional"))
    )
    (net (code "37") (name "Net-(IC18-EECLK)") (class "Default")
      (node (ref "IC18") (pin "56") (pinfunction "EECLK_56") (pintype "output"))
      (node (ref "IC21") (pin "2") (pinfunction "C_2") (pintype "input"))
      (node (ref "R203") (pin "1") (pinfunction "1_1") (pintype "passive"))
    )
    (net (code "38") (name "Net-(IC18-EECS)") (class "Default")
      (node (ref "IC18") (pin "1") (pinfunction "EECS_1") (pintype "bidirectional"))
      (node (ref "IC21") (pin "1") (pinfunction "S_1") (pintype "input"))
      (node (ref "R204") (pin "1") (pinfunction "1_1") (pintype "passive"))
    )
    (net (code "39") (name "Net-(IC18-EEDATA)") (class "Default")
      (node (ref "IC18") (pin "55") (pinfunction "EEDATA_55") (pintype "bidirectional"))
      (node (ref "IC21") (pin "3") (pinfunction "D_3") (pintype "input"))
      (node (ref "R205") (pin "2") (pinfunction "2_2") (pintype "passive"))
    )
    (net (code "40") (name "Net-(IC18-OSCI)") (class "Default")
      (node (ref "C207") (pin "2") (pinfunction "2_2") (pintype "passive"))
      (node (ref "IC18") (pin "3") (pinfunction "OSCI_3") (pintype "input"))
      (node (ref "Q2") (pin "1") (pinfunction "X_1") (pintype "passive"))
      (node (ref "TP15") (pin "1") (pinfunction "1_1") (pintype "bidirectional"))
    )
    (net (code "41") (name "Net-(IC18-OSCO)") (class "Default")
      (node (ref "C208") (pin "2") (pinfunction "2_2") (pintype "passive"))
      (node (ref "IC18") (pin "4") (pinfunction "OSCO_4") (pintype "output"))
      (node (ref "Q2") (pin "3") (pinfunction "X_3") (pintype "passive"))
    )
    (net (code "42") (name "Net-(IC18-REF)") (class "Default")
      (node (ref "IC18") (pin "6") (pinfunction "REF_6") (pintype "input"))
      (node (ref "R199") (pin "2") (pinfunction "2_2") (pintype "passive"))
    )
    (net (code "43") (name "Net-(IC18-VPHY)") (class "Default")
      (node (ref "C209") (pin "2") (pinfunction "2_2") (pintype "passive"))
      (node (ref "C210") (pin "2") (pinfunction "2_2") (pintype "passive"))
      (node (ref "IC18") (pin "5") (pinfunction "VPHY_5") (pintype "power_in"))
      (node (ref "L24") (pin "2") (pinfunction "2_2") (pintype "passive"))
    )
    (net (code "44") (name "Net-(IC18-VPLL)") (class "Default")
      (node (ref "C211") (pin "2") (pinfunction "2_2") (pintype "passive"))
      (node (ref "C212") (pin "2") (pinfunction "2_2") (pintype "passive"))
      (node (ref "IC18") (pin "9") (pinfunction "VPLL_9") (pintype "power_in"))
      (node (ref "L25") (pin "2") (pinfunction "2_2") (pintype "passive"))
    )
    (net (code "45") (name "Net-(IC21-Q)") (class "Default")
      (node (ref "IC21") (pin "4") (pinfunction "Q_4") (pintype "output"))
      (node (ref "R202") (pin "1") (pinfunction "1_1") (pintype "passive"))
      (node (ref "R205") (pin "1") (pinfunction "1_1") (pintype "passive"))
    )
    (net (code "46") (name "Net-(IC22-VREF2)") (class "Default")
      (node (ref "IC22") (pin "7") (pinfunction "VREF2_7") (pintype "input"))
      (node (ref "R241") (pin "2") (pinfunction "2_2") (pintype "passive"))
    )
    (net (code "47") (name "Net-(IC26-EN)") (class "Default")
      (node (ref "C202") (pin "2") (pinfunction "2_2") (pintype "passive"))
      (node (ref "IC26") (pin "1") (pinfunction "IN_1") (pintype "input"))
      (node (ref "IC26") (pin "3") (pinfunction "EN_3") (pintype "input"))
      (node (ref "L22") (pin "2") (pinfunction "2_2") (pintype "passive"))
    )
    (net (code "48") (name "P1V8") (class "Default")
      (node (ref "C154") (pin "2") (pinfunction "2_2") (pintype "passive"))
      (node (ref "IC20") (pin "6") (pinfunction "VCCB_6") (pintype "power_in"))
    )
    (net (code "49") (name "P1V8_USB") (class "Default")
      (node (ref "C206") (pin "2") (pinfunction "2_2") (pintype "passive"))
      (node (ref "IC18") (pin "2") (pinfunction "VCORE_2") (pintype "power_in"))
      (node (ref "IC18") (pin "31") (pinfunction "VCORE_31") (pintype "power_in"))
      (node (ref "IC18") (pin "43") (pinfunction "VREGOUT_43") (pintype "output"))
    )
    (net (code "50") (name "P2V5") (class "Default")
      (node (ref "C156") (pin "2") (pinfunction "2_2") (pintype "passive"))
      (node (ref "C216") (pin "2") (pinfunction "2_2") (pintype "passive"))
      (node (ref "C217") (pin "2") (pinfunction "2_2") (pintype "passive"))
      (node (ref "C218") (pin "2") (pinfunction "2_2") (pintype "passive"))
      (node (ref "IC16") (pin "6") (pinfunction "VCCB_6") (pintype "power_in"))
      (node (ref "IC17") (pin "6") (pinfunction "VCCB_6") (pintype "power_in"))
      (node (ref "IC19") (pin "6") (pinfunction "VCCB_6") (pintype "power_in"))
      (node (ref "IC37") (pin "6") (pinfunction "VCCB_6") (pintype "power_in"))
      (node (ref "R400") (pin "2") (pinfunction "2_2") (pintype "passive"))
      (node (ref "R401") (pin "2") (pinfunction "2_2") (pintype "passive"))
      (node (ref "R402") (pin "2") (pinfunction "2_2") (pintype "passive"))
      (node (ref "R403") (pin "2") (pinfunction "2_2") (pintype "passive"))
    )
    (net (code "51") (name "P3V3") (class "Default")
      (node (ref "C220") (pin "2") (pinfunction "2_2") (pintype "passive"))
      (node (ref "C54") (pin "2") (pinfunction "2_2") (pintype "passive"))
      (node (ref "IC22") (pin "2") (pinfunction "VREF1_2") (pintype "input"))
      (node (ref "IC9") (pin "6") (pinfunction "VCCB_6") (pintype "power_in"))
      (node (ref "R209") (pin "2") (pinfunction "2_2") (pintype "passive"))
    )
    (net (code "52") (name "P3V3_USB") (class "Default")
      (node (ref "C155") (pin "2") (pinfunction "2_2") (pintype "passive"))
      (node (ref "C204") (pin "2") (pinfunction "2_2") (pintype "passive"))
      (node (ref "C205") (pin "2") (pinfunction "2_2") (pintype "passive"))
      (node (ref "C213") (pin "2") (pinfunction "2_2") (pintype "passive"))
      (node (ref "C214") (pin "2") (pinfunction "2_2") (pintype "passive"))
      (node (ref "C215") (pin "2") (pinfunction "2_2") (pintype "passive"))
      (node (ref "C219") (pin "2") (pinfunction "2_2") (pintype "passive"))
      (node (ref "C221") (pin "2") (pinfunction "2_2") (pintype "passive"))
      (node (ref "C222") (pin "2") (pinfunction "2_2") (pintype "passive"))
      (node (ref "C223") (pin "2") (pinfunction "2_2") (pintype "passive"))
      (node (ref "C224") (pin "2") (pinfunction "2_2") (pintype "passive"))
      (node (ref "C57") (pin "2") (pinfunction "2_2") (pintype "passive"))
      (node (ref "C58") (pin "2") (pinfunction "2_2") (pintype "passive"))
      (node (ref "IC16") (pin "1") (pinfunction "DIR2_1") (pintype "input"))
      (node (ref "IC16") (pin "10") (pinfunction "DIR1_10") (pintype "input"))
      (node (ref "IC16") (pin "7") (pinfunction "VCCA_7") (pintype "power_in"))
      (node (ref "IC17") (pin "1") (pinfunction "DIR2_1") (pintype "input"))
      (node (ref "IC17") (pin "10") (pinfunction "DIR1_10") (pintype "input"))
      (node (ref "IC17") (pin "7") (pinfunction "VCCA_7") (pintype "power_in"))
      (node (ref "IC18") (pin "16") (pinfunction "VCCIO_16") (pintype "power_in"))
      (node (ref "IC18") (pin "36") (pinfunction "VCCIO_36") (pintype "power_in"))
      (node (ref "IC18") (pin "44") (pinfunction "VREGIN_44") (pintype "input"))
      (node (ref "IC18") (pin "50") (pinfunction "VCCIO_50") (pintype "power_in"))
      (node (ref "IC19") (pin "10") (pinfunction "DIR1_10") (pintype "input"))
      (node (ref "IC19") (pin "7") (pinfunction "VCCA_7") (pintype "power_in"))
      (node (ref "IC20") (pin "1") (pinfunction "DIR2_1") (pintype "input"))
      (node (ref "IC20") (pin "7") (pinfunction "VCCA_7") (pintype "power_in"))
      (node (ref "IC21") (pin "6") (pinfunction "ORG_6") (pintype "input"))
      (node (ref "IC21") (pin "8") (pinfunction "VCC_8") (pintype "power_in"))
      (node (ref "IC26") (pin "5") (pinfunction "OUT_5") (pintype "power_in"))
      (node (ref "IC37") (pin "1") (pinfunction "DIR2_1") (pintype "input"))
      (node (ref "IC37") (pin "7") (pinfunction "VCCA_7") (pintype "power_in"))
      (node (ref "IC9") (pin "1") (pinfunction "DIR2_1") (pintype "input"))
      (node (ref "IC9") (pin "10") (pinfunction "DIR1_10") (pintype "input"))
      (node (ref "IC9") (pin "7") (pinfunction "VCCA_7") (pintype "power_in"))
      (node (ref "L24") (pin "1") (pinfunction "1_1") (pintype "passive"))
      (node (ref "L25") (pin "1") (pinfunction "1_1") (pintype "passive"))
      (node (ref "R194") (pin "2") (pinfunction "2_2") (pintype "passive"))
      (node (ref "R195") (pin "2") (pinfunction "2_2") (pintype "passive"))
      (node (ref "R196") (pin "2") (pinfunction "2_2") (pintype "passive"))
      (node (ref "R197") (pin "2") (pinfunction "2_2") (pintype "passive"))
      (node (ref "R198") (pin "2") (pinfunction "2_2") (pintype "passive"))
      (node (ref "R202") (pin "2") (pinfunction "2_2") (pintype "passive"))
      (node (ref "R203") (pin "2") (pinfunction "2_2") (pintype "passive"))
      (node (ref "R204") (pin "2") (pinfunction "2_2") (pintype "passive"))
      (node (ref "R206") (pin "2") (pinfunction "2_2") (pintype "passive"))
      (node (ref "R207") (pin "2") (pinfunction "2_2") (pintype "passive"))
      (node (ref "R241") (pin "1") (pinfunction "1_1") (pintype "passive"))
    )
    (net (code "53") (name "unconnected-(IC9-B2-Pad4)") (class "Default")
      (node (ref "IC9") (pin "4") (pinfunction "B2_4") (pintype "bidirectional"))
    )
    (net (code "54") (name "unconnected-(IC16-B2-Pad4)") (class "Default")
      (node (ref "IC16") (pin "4") (pinfunction "B2_4") (pintype "bidirectional"))
    )
    (net (code "55") (name "unconnected-(IC18-ADBUS4-Pad17)") (class "Default")
      (node (ref "IC18") (pin "17") (pinfunction "ADBUS4_17") (pintype "bidirectional+no_connect"))
    )
    (net (code "56") (name "unconnected-(IC18-ADBUS5-Pad18)") (class "Default")
      (node (ref "IC18") (pin "18") (pinfunction "ADBUS5_18") (pintype "bidirectional+no_connect"))
    )
    (net (code "57") (name "unconnected-(IC18-BDBUS3-Pad25)") (class "Default")
      (node (ref "IC18") (pin "25") (pinfunction "BDBUS3_25") (pintype "bidirectional+no_connect"))
    )
    (net (code "58") (name "unconnected-(IC18-BDBUS4-Pad26)") (class "Default")
      (node (ref "IC18") (pin "26") (pinfunction "BDBUS4_26") (pintype "bidirectional"))
    )
    (net (code "59") (name "unconnected-(IC18-BDBUS7-Pad29)") (class "Default")
      (node (ref "IC18") (pin "29") (pinfunction "BDBUS7_29") (pintype "bidirectional+no_connect"))
    )
    (net (code "60") (name "unconnected-(IC18-CDBUS2-Pad34)") (class "Default")
      (node (ref "IC18") (pin "34") (pinfunction "CDBUS2_34") (pintype "bidirectional+no_connect"))
    )
    (net (code "61") (name "unconnected-(IC18-CDBUS3-Pad35)") (class "Default")
      (node (ref "IC18") (pin "35") (pinfunction "CDBUS3_35") (pintype "bidirectional+no_connect"))
    )
    (net (code "62") (name "unconnected-(IC18-CDBUS4-Pad37)") (class "Default")
      (node (ref "IC18") (pin "37") (pinfunction "CDBUS4_37") (pintype "bidirectional+no_connect"))
    )
    (net (code "63") (name "unconnected-(IC18-CDBUS5-Pad38)") (class "Default")
      (node (ref "IC18") (pin "38") (pinfunction "CDBUS5_38") (pintype "bidirectional+no_connect"))
    )
    (net (code "64") (name "unconnected-(IC18-CDBUS6-Pad39)") (class "Default")
      (node (ref "IC18") (pin "39") (pinfunction "CDBUS6_39") (pintype "bidirectional+no_connect"))
    )
    (net (code "65") (name "unconnected-(IC18-CDBUS7-Pad40)") (class "Default")
      (node (ref "IC18") (pin "40") (pinfunction "CDBUS7_40") (pintype "bidirectional+no_connect"))
    )
    (net (code "66") (name "unconnected-(IC18-DDBUS2-Pad47)") (class "Default")
      (node (ref "IC18") (pin "47") (pinfunction "DDBUS2_47") (pintype "bidirectional+no_connect"))
    )
    (net (code "67") (name "unconnected-(IC18-DDBUS3-Pad48)") (class "Default")
      (node (ref "IC18") (pin "48") (pinfunction "DDBUS3_48") (pintype "bidirectional+no_connect"))
    )
    (net (code "68") (name "unconnected-(IC18-DDBUS4-Pad49)") (class "Default")
      (node (ref "IC18") (pin "49") (pinfunction "DDBUS4_49") (pintype "bidirectional+no_connect"))
    )
    (net (code "69") (name "unconnected-(IC18-DDBUS5-Pad51)") (class "Default")
      (node (ref "IC18") (pin "51") (pinfunction "DDBUS5_51") (pintype "bidirectional+no_connect"))
    )
    (net (code "70") (name "unconnected-(IC18-DDBUS6-Pad52)") (class "Default")
      (node (ref "IC18") (pin "52") (pinfunction "DDBUS6_52") (pintype "bidirectional+no_connect"))
    )
    (net (code "71") (name "unconnected-(IC18-DDBUS7-Pad53)") (class "Default")
      (node (ref "IC18") (pin "53") (pinfunction "DDBUS7_53") (pintype "bidirectional+no_connect"))
    )
    (net (code "72") (name "unconnected-(IC18-~{PWREN}-Pad54)") (class "Default")
      (node (ref "IC18") (pin "54") (pinfunction "~{PWREN}_54") (pintype "output+no_connect"))
    )
    (net (code "73") (name "unconnected-(IC18-~{SUSPEND}-Pad30)") (class "Default")
      (node (ref "IC18") (pin "30") (pinfunction "~{SUSPEND}_30") (pintype "output+no_connect"))
    )
    (net (code "74") (name "unconnected-(IC21-DU-Pad7)") (class "Default")
      (node (ref "IC21") (pin "7") (pinfunction "DU_7") (pintype "passive+no_connect"))
    )
    (net (code "75") (name "unconnected-(IC26-BYP-Pad4)") (class "Default")
      (node (ref "IC26") (pin "4") (pinfunction "BYP_4") (pintype "passive+no_connect"))
    )
    (net (code "76") (name "unconnected-(J23-ID-Pad4)") (class "Default")
      (node (ref "J23") (pin "4") (pinfunction "ID_4") (pintype "passive+no_connect"))
    )
  )
)
